# LPCB222_-_SWITCH_INTERFACE.net
KiCad netlist of a schematic drawn in Altium Designer
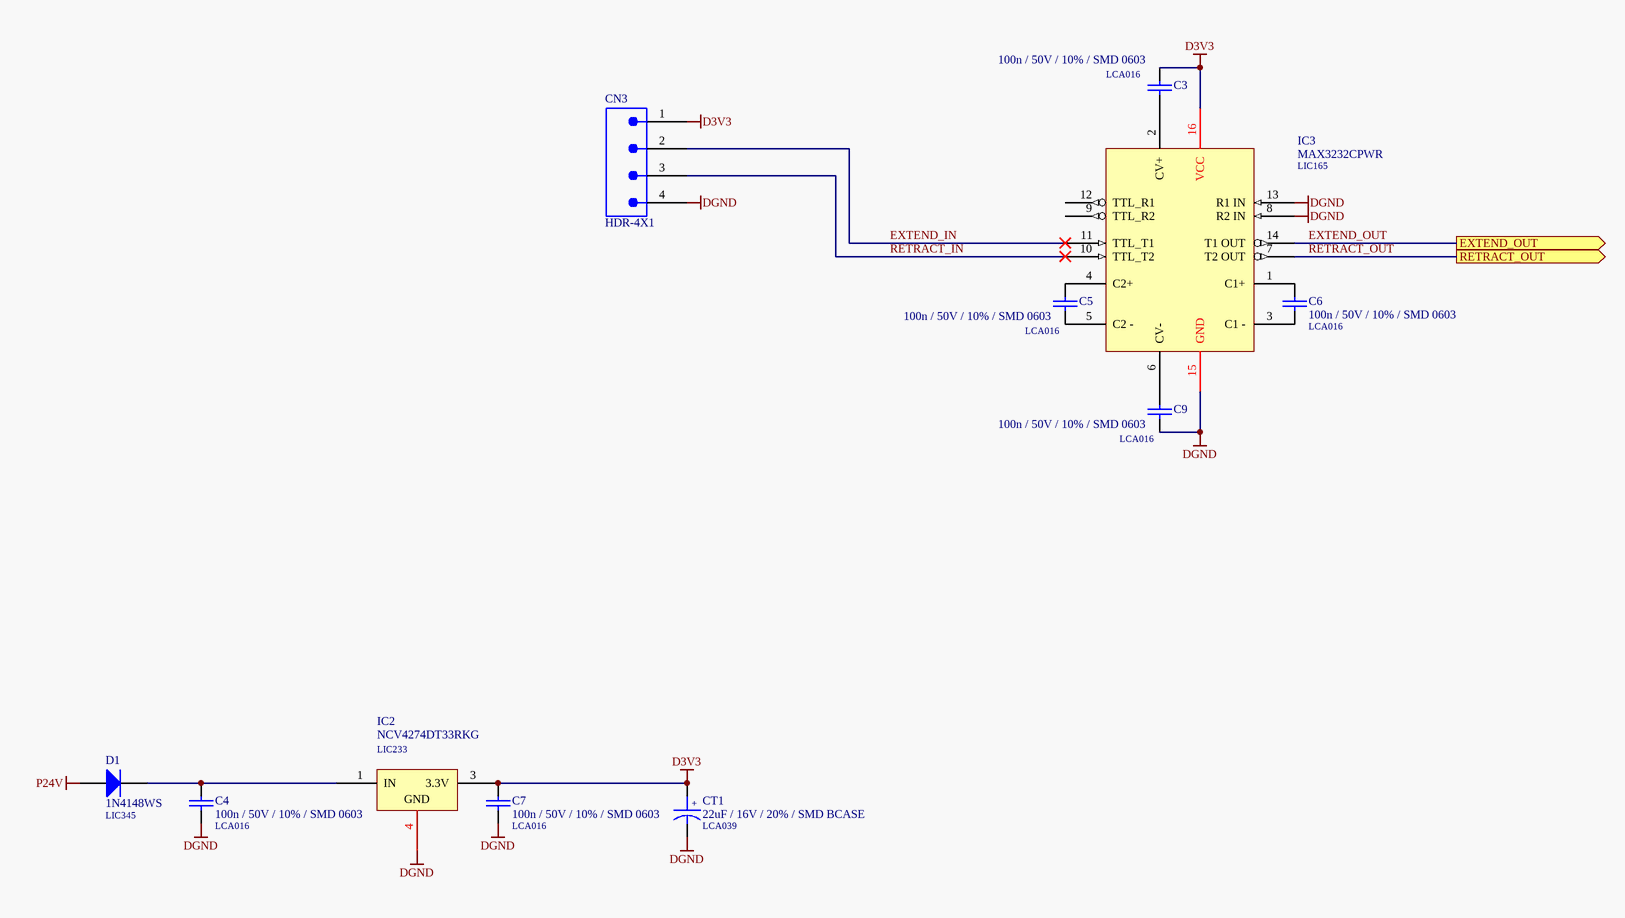
[diagram p0: LPCB222 - SWITCH INTERFACE.SchDoc]

(export (version "E")
  (design (tool "Eeschema 10.0.6"))
  (components
    (comp (ref "C3")
      (value "100n / 50V / 10% / SMD 0603")
      (footprint "LFP011__CC1608-0603-IPC7351_B")
      (description "Capacitor, Ceramic Chip, 100nF (0.1uF), 50V, 5%, SMD 0603 [LCA016]")
      (fields (field (name "LDL_NUMBER") "LCA016"))
      (libsource (lib "LDL_Capacitors") (part "100n / 50V / 10% / SMD 0603"))
    )
    (comp (ref "C4")
      (value "100n / 50V / 10% / SMD 0603")
      (footprint "LFP011__CC1608-0603-IPC7351_B")
      (description "Capacitor, Ceramic Chip, 100nF, 50V, 10%, SMD 0603")
      (fields (field (name "LDL_NUMBER") "LCA016"))
      (libsource (lib "LDL_Capacitors") (part "100n / 50V / 10% / SMD 0603"))
    )
    (comp (ref "C5")
      (value "100n / 50V / 10% / SMD 0603")
      (footprint "LFP011__CC1608-0603-IPC7351_B")
      (description "Capacitor, Ceramic Chip, 100nF (0.1uF), 50V, 5%, SMD 0603 [LCA016]")
      (fields (field (name "LDL_NUMBER") "LCA016"))
      (libsource (lib "LDL_Capacitors") (part "100n / 50V / 10% / SMD 0603"))
    )
    (comp (ref "C6")
      (value "100n / 50V / 10% / SMD 0603")
      (footprint "LFP011__CC1608-0603-IPC7351_B")
      (description "Capacitor, Ceramic Chip, 100nF (0.1uF), 50V, 5%, SMD 0603 [LCA016]")
      (fields (field (name "LDL_NUMBER") "LCA016"))
      (libsource (lib "LDL_Capacitors") (part "100n / 50V / 10% / SMD 0603"))
    )
    (comp (ref "C7")
      (value "100n / 50V / 10% / SMD 0603")
      (footprint "LFP011__CC1608-0603-IPC7351_B")
      (description "Capacitor, Ceramic Chip, 100nF, 50V, 10%, SMD 0603")
      (fields (field (name "LDL_NUMBER") "LCA016"))
      (libsource (lib "LDL_Capacitors") (part "100n / 50V / 10% / SMD 0603"))
    )
    (comp (ref "C9")
      (value "100n / 50V / 10% / SMD 0603")
      (footprint "LFP011__CC1608-0603-IPC7351_B")
      (description "Capacitor, Ceramic Chip, 100nF (0.1uF), 50V, 5%, SMD 0603 [LCA016]")
      (fields (field (name "LDL_NUMBER") "LCA016"))
      (libsource (lib "LDL_Capacitors") (part "100n / 50V / 10% / SMD 0603"))
    )
    (comp (ref "CN3")
      (value "HDR-4X1")
      (footprint "HDR-4X1")
      (description "Header, 2.54mm (0.1in), 4 Pins x 1 Row (40 Per Row In Strip)")
      (libsource (lib "LDL_Connectors") (part "HDR-4X1"))
    )
    (comp (ref "CT1")
      (value "22uF / 16V / 20% / SMD BCASE")
      (footprint "LFP018__TC3528")
      (description "Capacitor, Tantalum, 22uF, 16V, 20%, SMD B-Case")
      (fields (field (name "LDL_NUMBER") "LCA039"))
      (libsource (lib "LDL_Capacitors") (part "22uF / 16V / 20% / SMD BCASE"))
    )
    (comp (ref "D1")
      (value "1N4148WS")
      (footprint "LFP001__SOD-323F")
      (description "Diode, Small Signal, SMD SOD-323F")
      (fields (field (name "LDL_NUMBER") "LIC345"))
      (libsource (lib "LDL_Semiconductors") (part "1N4148WS"))
    )
    (comp (ref "IC2")
      (value "NCV4274DT33RKG")
      (footprint "LFP019__369A-13")
      (description "IC, Voltage Regulator, 400mA, 3.3V LDO, SMD DPAK [LIC233]")
      (fields (field (name "LDL_NUMBER") "LIC233"))
      (libsource (lib "LDL_Semiconductors") (part "NCV4274DT33RKG"))
    )
    (comp (ref "IC3")
      (value "MAX3232CPWR")
      (footprint "LFP049__TSSOP-16")
      (description "IC, RS232 Line Driver, 3.3V, SMD TSSOP16 [LIC165]")
      (fields (field (name "LDL_NUMBER") "LIC165"))
      (libsource (lib "LDL_Semiconductors") (part "MAX3232CPWR"))
    )
  )
  (nets
    (net (code "1") (name "/EXTEND_IN") (class "Default")
      (node (ref "CN3") (pin "2") (pinfunction "2_2") (pintype "passive"))
      (node (ref "IC3") (pin "11") (pinfunction "TTL_T1_11") (pintype "input"))
    )
    (net (code "2") (name "/EXTEND_OUT") (class "Default")
      (node (ref "IC3") (pin "14") (pinfunction "T1_OUT_14") (pintype "output"))
    )
    (net (code "3") (name "/RETRACT_IN") (class "Default")
      (node (ref "CN3") (pin "3") (pinfunction "3_3") (pintype "passive"))
      (node (ref "IC3") (pin "10") (pinfunction "TTL_T2_10") (pintype "input"))
    )
    (net (code "4") (name "/RETRACT_OUT") (class "Default")
      (node (ref "IC3") (pin "7") (pinfunction "T2_OUT_7") (pintype "output"))
    )
    (net (code "5") (name "D3V3") (class "Default")
      (node (ref "C3") (pin "1") (pintype "passive"))
      (node (ref "C7") (pin "1") (pintype "passive"))
      (node (ref "CN3") (pin "1") (pinfunction "1_1") (pintype "passive"))
      (node (ref "CT1") (pin "1") (pinfunction "1_1") (pintype "passive"))
      (node (ref "IC2") (pin "3") (pinfunction "3.3V_3") (pintype "power_in"))
      (node (ref "IC3") (pin "16") (pinfunction "VCC_16") (pintype "power_in"))
    )
    (net (code "6") (name "DGND") (class "Default")
      (node (ref "C4") (pin "2") (pintype "passive"))
      (node (ref "C7") (pin "2") (pintype "passive"))
      (node (ref "C9") (pin "2") (pintype "passive"))
      (node (ref "CN3") (pin "4") (pinfunction "4_4") (pintype "passive"))
      (node (ref "CT1") (pin "2") (pinfunction "2_2") (pintype "passive"))
      (node (ref "IC2") (pin "4") (pinfunction "GND_4") (pintype "power_in"))
      (node (ref "IC3") (pin "13") (pinfunction "R1_IN_13") (pintype "input"))
      (node (ref "IC3") (pin "15") (pinfunction "GND_15") (pintype "power_in"))
      (node (ref "IC3") (pin "8") (pinfunction "R2_IN_8") (pintype "input"))
    )
    (net (code "7") (name "Net-(D1-K)") (class "Default")
      (node (ref "C4") (pin "1") (pintype "passive"))
      (node (ref "D1") (pin "1") (pinfunction "K_1") (pintype "passive"))
      (node (ref "IC2") (pin "1") (pinfunction "IN_1") (pintype "power_in"))
    )
    (net (code "8") (name "Net-(IC3-C1+)") (class "Default")
      (node (ref "C6") (pin "1") (pintype "passive"))
      (node (ref "IC3") (pin "1") (pinfunction "C1+_1") (pintype "passive"))
    )
    (net (code "9") (name "Net-(IC3-C1_-)") (class "Default")
      (node (ref "C6") (pin "2") (pintype "passive"))
      (node (ref "IC3") (pin "3") (pinfunction "C1_-_3") (pintype "passive"))
    )
    (net (code "10") (name "Net-(IC3-C2+)") (class "Default")
      (node (ref "C5") (pin "1") (pintype "passive"))
      (node (ref "IC3") (pin "4") (pinfunction "C2+_4") (pintype "passive"))
    )
    (net (code "11") (name "Net-(IC3-C2_-)") (class "Default")
      (node (ref "C5") (pin "2") (pintype "passive"))
      (node (ref "IC3") (pin "5") (pinfunction "C2_-_5") (pintype "passive"))
    )
    (net (code "12") (name "Net-(IC3-CV+)") (class "Default")
      (node (ref "C3") (pin "2") (pintype "passive"))
      (node (ref "IC3") (pin "2") (pinfunction "CV+_2") (pintype "passive"))
    )
    (net (code "13") (name "Net-(IC3-CV-)") (class "Default")
      (node (ref "C9") (pin "1") (pintype "passive"))
      (node (ref "IC3") (pin "6") (pinfunction "CV-_6") (pintype "passive"))
    )
    (net (code "14") (name "P24V") (class "Default")
      (node (ref "D1") (pin "2") (pinfunction "A_2") (pintype "passive"))
    )
    (net (code "15") (name "unconnected-(IC3-TTL_R1-Pad12)") (class "Default")
      (node (ref "IC3") (pin "12") (pinfunction "TTL_R1_12") (pintype "output"))
    )
    (net (code "16") (name "unconnected-(IC3-TTL_R2-Pad9)") (class "Default")
      (node (ref "IC3") (pin "9") (pinfunction "TTL_R2_9") (pintype "output"))
    )
  )
)
